# PWR.net
KiCad netlist of a schematic drawn in Altium Designer
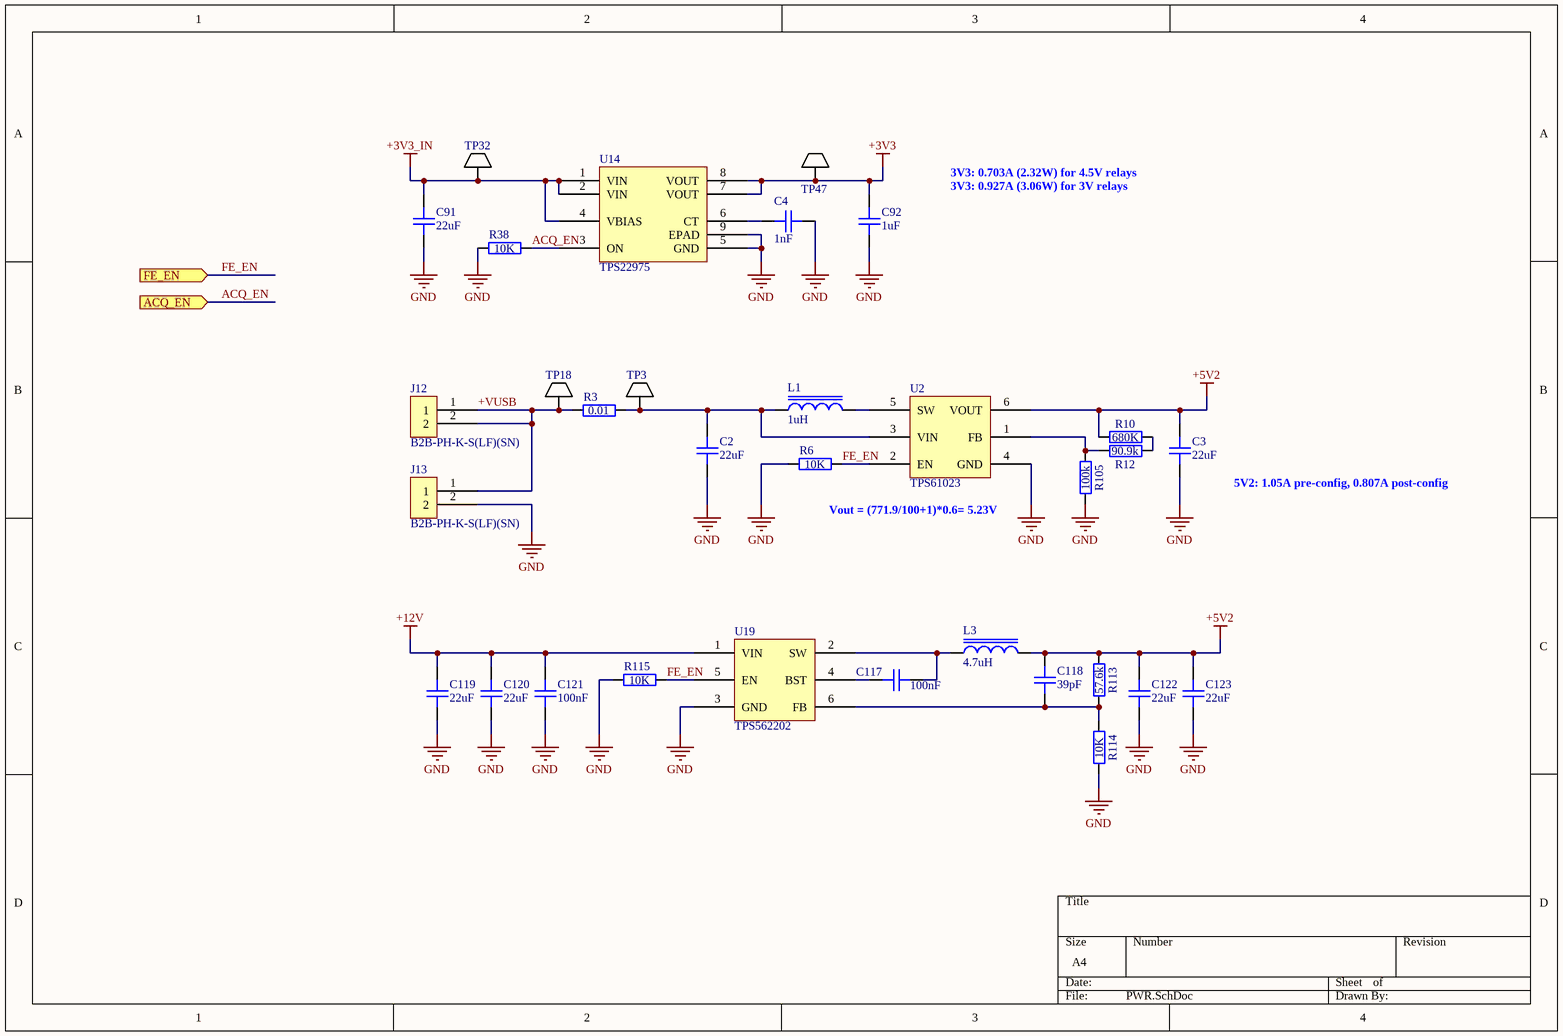
[diagram p0: PWR.SchDoc]

(export (version "E")
  (design (tool "Eeschema 10.0.6"))
  (components
    (comp (ref "C2")
      (value "22uF")
      (footprint "GEN_C_0805")
      (libsource (lib "DSO") (part "CAP 22uF 25V X5R 0805"))
    )
    (comp (ref "C3")
      (value "22uF")
      (footprint "GEN_C_0805")
      (libsource (lib "DSO") (part "CAP 22uF 25V X5R 0805"))
    )
    (comp (ref "C4")
      (value "1nF")
      (footprint "GEN_C_0402")
      (libsource (lib "DSO") (part "CAP 1nF 50V C0G 0402"))
    )
    (comp (ref "C91")
      (value "22uF")
      (footprint "GEN_C_0805")
      (libsource (lib "DSO") (part "CAP 22uF 25V X5R 0805"))
    )
    (comp (ref "C92")
      (value "1uF")
      (footprint "GEN_C_0402")
      (libsource (lib "DSO") (part "CAP 1uF 25V X5R 0402"))
    )
    (comp (ref "C117")
      (value "100nF")
      (footprint "GEN_C_0402")
      (libsource (lib "DSO") (part "CAP 100nF 16V X7R 0402"))
    )
    (comp (ref "C118")
      (value "39pF")
      (footprint "GEN_C_0402")
      (fields
        (field (name "MANUFACTURER") "KEMET")
        (field (name "HOUSE PART NUMBER") "C-39pF-0402-002")
        (field (name "MANUFACTURER PART NUMBER") "C0402C390J5GACTU")
      )
      (libsource (lib "DSO") (part "CAP 39pF 50V C0G 0402"))
    )
    (comp (ref "C119")
      (value "22uF")
      (footprint "GEN_C_0805")
      (libsource (lib "DSO") (part "CAP 22uF 25V X5R 0805"))
    )
    (comp (ref "C120")
      (value "22uF")
      (footprint "GEN_C_0805")
      (libsource (lib "DSO") (part "CAP 22uF 25V X5R 0805"))
    )
    (comp (ref "C121")
      (value "100nF")
      (footprint "GEN_C_0402")
      (libsource (lib "DSO") (part "CAP 100nF 16V X7R 0402"))
    )
    (comp (ref "C122")
      (value "22uF")
      (footprint "GEN_C_0805")
      (libsource (lib "DSO") (part "CAP 22uF 25V X5R 0805"))
    )
    (comp (ref "C123")
      (value "22uF")
      (footprint "GEN_C_0805")
      (libsource (lib "DSO") (part "CAP 22uF 25V X5R 0805"))
    )
    (comp (ref "J12")
      (value "B2B-PH-K-S(LF)(SN)")
      (footprint "JST_B2B-PH-K-S(LF)(SN)")
      (libsource (lib "DSO") (part "CONN JST PH 2 Pin TH"))
    )
    (comp (ref "J13")
      (value "B2B-PH-K-S(LF)(SN)")
      (footprint "JST_B2B-PH-K-S(LF)(SN)")
      (libsource (lib "DSO") (part "CONN JST PH 2 Pin TH"))
    )
    (comp (ref "L1")
      (value "1uH")
      (footprint "GEN_L_1210")
      (libsource (lib "DSO") (part "IND 1uH 3.1A 45 MOHM 1210"))
    )
    (comp (ref "L3")
      (value "4.7uH")
      (footprint "TY_IND_NRS5030")
      (libsource (lib "DSO") (part "IND 4.7uH 2.6A 35 MOHM SMD"))
    )
    (comp (ref "R3")
      (value "0.01")
      (footprint "GEN_R_0603")
      (fields (field (name "TOLERANCE") "1%"))
      (libsource (lib "DSO") (part "RES 0.01 OHM 1% 1/4W 0603"))
    )
    (comp (ref "R6")
      (value "10K")
      (footprint "GEN_R_0402")
      (fields (field (name "TOLERANCE") "1%"))
      (libsource (lib "DSO") (part "RES 10K OHM 1% 1/10W 0402"))
    )
    (comp (ref "R10")
      (value "680K")
      (footprint "GEN_R_0402")
      (fields
        (field (name "TOLERANCE") "1%")
        (field (name "MANUFACTURER") "Yageo")
        (field (name "MANUFACTURER PART NUMBER") "RC0402FR-07681KL")
      )
      (libsource (lib "DSO") (part "RES 680K OHM 1% 1/16W 0402"))
    )
    (comp (ref "R12")
      (value "90.9k")
      (footprint "GEN_R_0402")
      (fields (field (name "TOLERANCE") "1%"))
      (libsource (lib "DSO") (part "RES 90.9K OHM 1% 1/16W 0402"))
    )
    (comp (ref "R38")
      (value "10K")
      (footprint "GEN_R_0402")
      (fields (field (name "TOLERANCE") "1%"))
      (libsource (lib "") (part "RES 10K OHM 1% 1/10W 0402_1"))
    )
    (comp (ref "R105")
      (value "100k")
      (footprint "GEN_R_0402")
      (fields (field (name "TOLERANCE") "1%"))
      (libsource (lib "DSO") (part "RES 100K OHM 1% 1/10W 0402"))
    )
    (comp (ref "R113")
      (value "57.6k")
      (footprint "GEN_R_0402")
      (fields (field (name "TOLERANCE") "1%"))
      (libsource (lib "DSO") (part "RES 57.6K OHM 1% 1/16W 0402"))
    )
    (comp (ref "R114")
      (value "10K")
      (footprint "GEN_R_0402")
      (fields (field (name "TOLERANCE") "1%"))
      (libsource (lib "") (part "RES 10K OHM 1% 1/10W 0402_1"))
    )
    (comp (ref "R115")
      (value "10K")
      (footprint "GEN_R_0402")
      (fields (field (name "TOLERANCE") "1%"))
      (libsource (lib "DSO") (part "RES 10K OHM 1% 1/10W 0402"))
    )
    (comp (ref "TP3") (value "5015") (footprint "KEY_5015") (libsource (lib "DSO") (part "TP KEYSTONE 5015")))
    (comp (ref "TP18")
      (value "5015")
      (footprint "KEY_5015")
      (libsource (lib "DSO") (part "TP KEYSTONE 5015"))
    )
    (comp (ref "TP32")
      (value "5015")
      (footprint "KEY_5015")
      (libsource (lib "DSO") (part "TP KEYSTONE 5015"))
    )
    (comp (ref "TP47")
      (value "5015")
      (footprint "KEY_5015")
      (libsource (lib "DSO") (part "TP KEYSTONE 5015"))
    )
    (comp (ref "U2")
      (value "TPS61023")
      (footprint "TI_SOT563_DRL0006A")
      (libsource (lib "DSO") (part "IC BOOST TPS61023"))
    )
    (comp (ref "U14")
      (value "TPS22975")
      (footprint "TI_WSON8_DSG0008A")
      (libsource (lib "DSO") (part "IC SWITCH LOAD TPS22975"))
    )
    (comp (ref "U19")
      (value "TPS562202")
      (footprint "TI_SOT563_DRL0006A")
      (libsource (lib "DSO") (part "IC BUCK TPS562202"))
    )
  )
  (nets
    (net (code "1") (name "+3V3") (class "Default")
      (node (ref "C92") (pin "2") (pinfunction "2_2") (pintype "passive"))
      (node (ref "TP47") (pin "1") (pinfunction "1_1") (pintype "passive"))
      (node (ref "U14") (pin "7") (pinfunction "VOUT_7") (pintype "passive"))
      (node (ref "U14") (pin "8") (pinfunction "VOUT_8") (pintype "passive"))
    )
    (net (code "2") (name "+3V3_IN") (class "Default")
      (node (ref "C91") (pin "2") (pinfunction "2_2") (pintype "passive"))
      (node (ref "TP32") (pin "1") (pinfunction "1_1") (pintype "passive"))
      (node (ref "U14") (pin "1") (pinfunction "VIN_1") (pintype "passive"))
      (node (ref "U14") (pin "2") (pinfunction "VIN_2") (pintype "passive"))
      (node (ref "U14") (pin "4") (pinfunction "VBIAS_4") (pintype "passive"))
    )
    (net (code "3") (name "+5V2") (class "Default")
      (node (ref "C118") (pin "2") (pinfunction "2_2") (pintype "passive"))
      (node (ref "C122") (pin "2") (pinfunction "2_2") (pintype "passive"))
      (node (ref "C123") (pin "2") (pinfunction "2_2") (pintype "passive"))
      (node (ref "C3") (pin "2") (pinfunction "2_2") (pintype "passive"))
      (node (ref "L3") (pin "2") (pinfunction "2_2") (pintype "passive"))
      (node (ref "R10") (pin "2") (pinfunction "2_2") (pintype "passive"))
      (node (ref "R113") (pin "2") (pinfunction "2_2") (pintype "passive"))
      (node (ref "U2") (pin "6") (pinfunction "VOUT_6") (pintype "passive"))
    )
    (net (code "4") (name "+12V") (class "Default")
      (node (ref "C119") (pin "2") (pinfunction "2_2") (pintype "passive"))
      (node (ref "C120") (pin "2") (pinfunction "2_2") (pintype "passive"))
      (node (ref "C121") (pin "1") (pinfunction "1_1") (pintype "passive"))
      (node (ref "U19") (pin "1") (pinfunction "VIN_1") (pintype "power_in"))
    )
    (net (code "5") (name "/+VUSB") (class "Default")
      (node (ref "J12") (pin "1") (pinfunction "1_1") (pintype "passive"))
      (node (ref "J12") (pin "2") (pinfunction "2_2") (pintype "passive"))
      (node (ref "J13") (pin "1") (pinfunction "1_1") (pintype "passive"))
      (node (ref "R3") (pin "2") (pinfunction "2_2") (pintype "passive"))
      (node (ref "TP18") (pin "1") (pinfunction "1_1") (pintype "passive"))
    )
    (net (code "6") (name "/ACQ_EN") (class "Default")
      (node (ref "R38") (pin "2") (pinfunction "2_2") (pintype "passive"))
      (node (ref "U14") (pin "3") (pinfunction "ON_3") (pintype "passive"))
    )
    (net (code "7") (name "/FE_EN") (class "Default")
      (node (ref "R115") (pin "1") (pinfunction "1_1") (pintype "passive"))
      (node (ref "R6") (pin "1") (pinfunction "1_1") (pintype "passive"))
      (node (ref "U19") (pin "5") (pinfunction "EN_5") (pintype "passive"))
      (node (ref "U2") (pin "2") (pinfunction "EN_2") (pintype "passive"))
    )
    (net (code "8") (name "GND") (class "Default")
      (node (ref "C119") (pin "1") (pinfunction "1_1") (pintype "passive"))
      (node (ref "C120") (pin "1") (pinfunction "1_1") (pintype "passive"))
      (node (ref "C121") (pin "2") (pinfunction "2_2") (pintype "passive"))
      (node (ref "C122") (pin "1") (pinfunction "1_1") (pintype "passive"))
      (node (ref "C123") (pin "1") (pinfunction "1_1") (pintype "passive"))
      (node (ref "C2") (pin "1") (pinfunction "1_1") (pintype "passive"))
      (node (ref "C3") (pin "1") (pinfunction "1_1") (pintype "passive"))
      (node (ref "C4") (pin "1") (pinfunction "1_1") (pintype "passive"))
      (node (ref "C91") (pin "1") (pinfunction "1_1") (pintype "passive"))
      (node (ref "C92") (pin "1") (pinfunction "1_1") (pintype "passive"))
      (node (ref "J13") (pin "2") (pinfunction "2_2") (pintype "passive"))
      (node (ref "R105") (pin "1") (pinfunction "1_1") (pintype "passive"))
      (node (ref "R114") (pin "1") (pinfunction "1_1") (pintype "passive"))
      (node (ref "R115") (pin "2") (pinfunction "2_2") (pintype "passive"))
      (node (ref "R38") (pin "1") (pinfunction "1_1") (pintype "passive"))
      (node (ref "R6") (pin "2") (pinfunction "2_2") (pintype "passive"))
      (node (ref "U14") (pin "5") (pinfunction "GND_5") (pintype "passive"))
      (node (ref "U14") (pin "9") (pinfunction "EPAD_9") (pintype "passive"))
      (node (ref "U19") (pin "3") (pinfunction "GND_3") (pintype "power_in"))
      (node (ref "U2") (pin "4") (pinfunction "GND_4") (pintype "power_in"))
    )
    (net (code "9") (name "Net-(R10-Pad1)") (class "Default")
      (node (ref "R10") (pin "1") (pinfunction "1_1") (pintype "passive"))
      (node (ref "R12") (pin "2") (pinfunction "2_2") (pintype "passive"))
    )
    (net (code "10") (name "Net-(U2-FB)") (class "Default")
      (node (ref "R105") (pin "2") (pinfunction "2_2") (pintype "passive"))
      (node (ref "R12") (pin "1") (pinfunction "1_1") (pintype "passive"))
      (node (ref "U2") (pin "1") (pinfunction "FB_1") (pintype "passive"))
    )
    (net (code "11") (name "Net-(U2-SW)") (class "Default")
      (node (ref "L1") (pin "2") (pinfunction "2_2") (pintype "passive"))
      (node (ref "U2") (pin "5") (pinfunction "SW_5") (pintype "passive"))
    )
    (net (code "12") (name "Net-(U2-VIN)") (class "Default")
      (node (ref "C2") (pin "2") (pinfunction "2_2") (pintype "passive"))
      (node (ref "L1") (pin "1") (pinfunction "1_1") (pintype "passive"))
      (node (ref "R3") (pin "1") (pinfunction "1_1") (pintype "passive"))
      (node (ref "TP3") (pin "1") (pinfunction "1_1") (pintype "passive"))
      (node (ref "U2") (pin "3") (pinfunction "VIN_3") (pintype "power_in"))
    )
    (net (code "13") (name "Net-(U14-CT)") (class "Default")
      (node (ref "C4") (pin "2") (pinfunction "2_2") (pintype "passive"))
      (node (ref "U14") (pin "6") (pinfunction "CT_6") (pintype "passive"))
    )
    (net (code "14") (name "Net-(U19-BST)") (class "Default")
      (node (ref "C117") (pin "2") (pinfunction "2_2") (pintype "passive"))
      (node (ref "U19") (pin "4") (pinfunction "BST_4") (pintype "passive"))
    )
    (net (code "15") (name "Net-(U19-FB)") (class "Default")
      (node (ref "C118") (pin "1") (pinfunction "1_1") (pintype "passive"))
      (node (ref "R113") (pin "1") (pinfunction "1_1") (pintype "passive"))
      (node (ref "R114") (pin "2") (pinfunction "2_2") (pintype "passive"))
      (node (ref "U19") (pin "6") (pinfunction "FB_6") (pintype "passive"))
    )
    (net (code "16") (name "Net-(U19-SW)") (class "Default")
      (node (ref "C117") (pin "1") (pinfunction "1_1") (pintype "passive"))
      (node (ref "L3") (pin "1") (pinfunction "1_1") (pintype "passive"))
      (node (ref "U19") (pin "2") (pinfunction "SW_2") (pintype "passive"))
    )
  )
)
